# 2_ADSTM32_MCU.net
KiCad netlist of a schematic drawn in Altium Designer
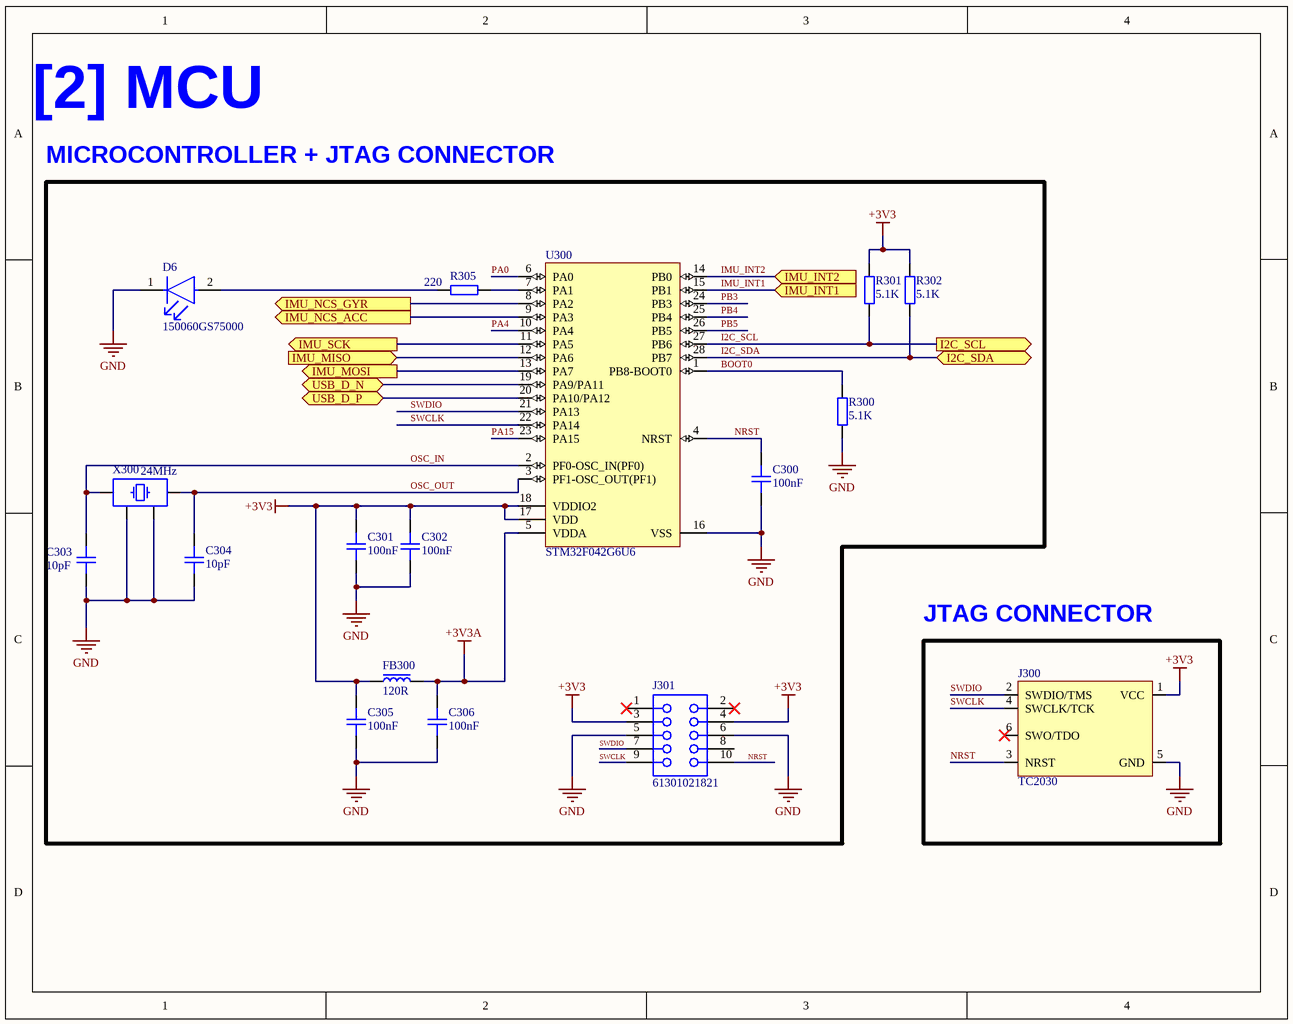
[diagram p0: 2_ADSTM32_MCU.SchDoc]

(export (version "E")
  (design (tool "Eeschema 10.0.6"))
  (components
    (comp (ref "C300")
      (value "100nF")
      (footprint "CAP_0603")
      (description "Capacitor SMD 0603 16V")
      (libsource (lib "Schematic-Lib-PhilsLab") (part "CAP_0603_16V"))
    )
    (comp (ref "C301")
      (value "100nF")
      (footprint "CAP_0603")
      (description "Capacitor SMD 0603 16V")
      (libsource (lib "Schematic-Lib-PhilsLab") (part "CAP_0603_16V"))
    )
    (comp (ref "C302")
      (value "100nF")
      (footprint "CAP_0603")
      (description "Capacitor SMD 0603 16V")
      (libsource (lib "Schematic-Lib-PhilsLab") (part "CAP_0603_16V"))
    )
    (comp (ref "C303")
      (value "10pF")
      (footprint "CAP_0603")
      (description "Capacitor SMD 0603 16V")
      (libsource (lib "Schematic-Lib-PhilsLab") (part "CAP_0603_16V"))
    )
    (comp (ref "C304")
      (value "10pF")
      (footprint "CAP_0603")
      (description "Capacitor SMD 0603 16V")
      (libsource (lib "Schematic-Lib-PhilsLab") (part "CAP_0603_16V"))
    )
    (comp (ref "C305")
      (value "100nF")
      (footprint "CAP_0603")
      (description "Capacitor SMD 0603 16V")
      (libsource (lib "Schematic-Lib-PhilsLab") (part "CAP_0603_16V"))
    )
    (comp (ref "C306")
      (value "100nF")
      (footprint "CAP_0603")
      (description "Capacitor SMD 0603 16V")
      (libsource (lib "Schematic-Lib-PhilsLab") (part "CAP_0603_16V"))
    )
    (comp (ref "D6")
      (value "150060GS75000")
      (footprint "FP-150060GS75000-MFG")
      (description "LED GREEN CLEAR 0603 SMD")
      (libsource (lib "Altium Content Vault") (part "8706943c75ba83719d021d2fdc84c58"))
    )
    (comp (ref "FB300")
      (value "120R")
      (footprint "FB_0603")
      (description "Ferrite Bead SMD 0603")
      (libsource (lib "Schematic-Lib-PhilsLab") (part "FB_0603"))
    )
    (comp (ref "J300")
      (value "TC2030")
      (footprint "TC2030-FP")
      (description "Tag-Connect No-Solder SWD Debug Connector DO NOT PLACE")
      (fields (field (name "MANUFACTURER") "Tag-Connect"))
      (libsource (lib "Schematic-Lib-PhilsLab") (part "TC2030"))
    )
    (comp (ref "J301")
      (value "61301021821")
      (footprint "61301021821")
      (libsource (lib "Altium Content Vault") (part "Header_Female_2R_10P"))
    )
    (comp (ref "R300")
      (value "5.1K")
      (footprint "RES_0603")
      (description "Resistor SMD 0603")
      (libsource (lib "Schematic-Lib-PhilsLab") (part "RES_0603"))
    )
    (comp (ref "R301")
      (value "5.1K")
      (footprint "RES_0603")
      (description "Resistor SMD 0603")
      (libsource (lib "Schematic-Lib-PhilsLab") (part "RES_0603"))
    )
    (comp (ref "R302")
      (value "5.1K")
      (footprint "RES_0603")
      (description "Resistor SMD 0603")
      (libsource (lib "Schematic-Lib-PhilsLab") (part "RES_0603"))
    )
    (comp (ref "R305")
      (value "220")
      (footprint "RES_0603")
      (description "Resistor SMD 0603")
      (libsource (lib "Schematic-Lib-PhilsLab") (part "RES_0603"))
    )
    (comp (ref "U300")
      (value "STM32F042G6U6")
      (footprint "STM-UFQFPN28_V")
      (fields (field (name "MANUFACTURER") "STMicroelectronics"))
      (libsource (lib "Altium Content Vault") (part "MC-ARM-STM32F042-UFQFPN28"))
    )
    (comp (ref "X300")
      (value "24MHz")
      (footprint "XTAL_3225")
      (description "Crystal SMD 24MHz 10PPM 7pF 3225")
      (fields
        (field (name "MANUFACTURER") "Epson")
        (field (name "MANUFACTURER PART NUMBER") "TSX-3225 24.0000MF15X-AC")
      )
      (libsource (lib "Schematic-Lib-PhilsLab") (part "TSX-3225_24.0000MF15X-AC"))
    )
  )
  (nets
    (net (code "1") (name "+3V3") (class "Default")
      (node (ref "C301") (pin "2") (pinfunction "2_2") (pintype "passive"))
      (node (ref "C302") (pin "2") (pinfunction "2_2") (pintype "passive"))
      (node (ref "C305") (pin "2") (pinfunction "2_2") (pintype "passive"))
      (node (ref "FB300") (pin "1") (pinfunction "1_1") (pintype "passive"))
      (node (ref "J300") (pin "1") (pinfunction "VCC_1") (pintype "passive"))
      (node (ref "J301") (pin "3") (pinfunction "3_3") (pintype "passive"))
      (node (ref "J301") (pin "4") (pinfunction "4_4") (pintype "passive"))
      (node (ref "R301") (pin "1") (pinfunction "1_1") (pintype "passive"))
      (node (ref "R302") (pin "1") (pinfunction "1_1") (pintype "passive"))
      (node (ref "U300") (pin "17") (pinfunction "VDD_17") (pintype "power_in"))
      (node (ref "U300") (pin "18") (pinfunction "VDDIO2_18") (pintype "power_in"))
    )
    (net (code "2") (name "+3V3A") (class "Default")
      (node (ref "C306") (pin "2") (pinfunction "2_2") (pintype "passive"))
      (node (ref "FB300") (pin "2") (pinfunction "2_2") (pintype "passive"))
      (node (ref "U300") (pin "5") (pinfunction "VDDA_5") (pintype "power_in"))
    )
    (net (code "3") (name "/BOOT0") (class "Default")
      (node (ref "R300") (pin "1") (pinfunction "1_1") (pintype "passive"))
      (node (ref "U300") (pin "1") (pinfunction "PB8-BOOT0_1") (pintype "bidirectional"))
    )
    (net (code "4") (name "/I2C_SCL") (class "Default")
      (node (ref "R301") (pin "2") (pinfunction "2_2") (pintype "passive"))
      (node (ref "U300") (pin "27") (pinfunction "PB6_27") (pintype "bidirectional"))
    )
    (net (code "5") (name "/I2C_SDA") (class "Default")
      (node (ref "R302") (pin "2") (pinfunction "2_2") (pintype "passive"))
      (node (ref "U300") (pin "28") (pinfunction "PB7_28") (pintype "bidirectional"))
    )
    (net (code "6") (name "/IMU_INT1") (class "Default")
      (node (ref "U300") (pin "15") (pinfunction "PB1_15") (pintype "bidirectional"))
    )
    (net (code "7") (name "/IMU_INT2") (class "Default")
      (node (ref "U300") (pin "14") (pinfunction "PB0_14") (pintype "bidirectional"))
    )
    (net (code "8") (name "/IMU_MISO") (class "Default")
      (node (ref "U300") (pin "12") (pinfunction "PA6_12") (pintype "bidirectional"))
    )
    (net (code "9") (name "/IMU_MOSI") (class "Default")
      (node (ref "U300") (pin "13") (pinfunction "PA7_13") (pintype "bidirectional"))
    )
    (net (code "10") (name "/IMU_NCS_ACC") (class "Default")
      (node (ref "U300") (pin "9") (pinfunction "PA3_9") (pintype "bidirectional"))
    )
    (net (code "11") (name "/IMU_NCS_GYR") (class "Default")
      (node (ref "U300") (pin "8") (pinfunction "PA2_8") (pintype "bidirectional"))
    )
    (net (code "12") (name "/IMU_SCK") (class "Default")
      (node (ref "U300") (pin "11") (pinfunction "PA5_11") (pintype "bidirectional"))
    )
    (net (code "13") (name "/NRST") (class "Default")
      (node (ref "C300") (pin "2") (pinfunction "2_2") (pintype "passive"))
      (node (ref "J300") (pin "3") (pinfunction "NRST_3") (pintype "passive"))
      (node (ref "J301") (pin "10") (pinfunction "10_10") (pintype "passive"))
      (node (ref "U300") (pin "4") (pinfunction "NRST_4") (pintype "bidirectional"))
    )
    (net (code "14") (name "/OSC_IN") (class "Default")
      (node (ref "C303") (pin "2") (pinfunction "2_2") (pintype "passive"))
      (node (ref "U300") (pin "2") (pinfunction "PF0-OSC_IN(PF0)_2") (pintype "bidirectional"))
      (node (ref "X300") (pin "1") (pinfunction "1_1") (pintype "passive"))
    )
    (net (code "15") (name "/OSC_OUT") (class "Default")
      (node (ref "C304") (pin "2") (pinfunction "2_2") (pintype "passive"))
      (node (ref "U300") (pin "3") (pinfunction "PF1-OSC_OUT(PF1)_3") (pintype "bidirectional"))
      (node (ref "X300") (pin "3") (pinfunction "3_3") (pintype "passive"))
    )
    (net (code "16") (name "/PA0") (class "Default")
      (node (ref "U300") (pin "6") (pinfunction "PA0_6") (pintype "bidirectional"))
    )
    (net (code "17") (name "/PA4") (class "Default")
      (node (ref "U300") (pin "10") (pinfunction "PA4_10") (pintype "bidirectional"))
    )
    (net (code "18") (name "/PA15") (class "Default")
      (node (ref "U300") (pin "23") (pinfunction "PA15_23") (pintype "bidirectional"))
    )
    (net (code "19") (name "/PB3") (class "Default")
      (node (ref "U300") (pin "24") (pinfunction "PB3_24") (pintype "bidirectional"))
    )
    (net (code "20") (name "/PB4") (class "Default")
      (node (ref "U300") (pin "25") (pinfunction "PB4_25") (pintype "bidirectional"))
    )
    (net (code "21") (name "/PB5") (class "Default")
      (node (ref "U300") (pin "26") (pinfunction "PB5_26") (pintype "bidirectional"))
    )
    (net (code "22") (name "/SWCLK") (class "Default")
      (node (ref "J300") (pin "4") (pinfunction "SWCLK/TCK_4") (pintype "passive"))
      (node (ref "J301") (pin "9") (pinfunction "9_9") (pintype "passive"))
      (node (ref "U300") (pin "22") (pinfunction "PA14_22") (pintype "bidirectional"))
    )
    (net (code "23") (name "/SWDIO") (class "Default")
      (node (ref "J300") (pin "2") (pinfunction "SWDIO/TMS_2") (pintype "passive"))
      (node (ref "J301") (pin "7") (pinfunction "7_7") (pintype "passive"))
      (node (ref "U300") (pin "21") (pinfunction "PA13_21") (pintype "bidirectional"))
    )
    (net (code "24") (name "/USB_D_N") (class "Default")
      (node (ref "U300") (pin "19") (pinfunction "PA9/PA11_19") (pintype "bidirectional"))
    )
    (net (code "25") (name "/USB_D_P") (class "Default")
      (node (ref "U300") (pin "20") (pinfunction "PA10/PA12_20") (pintype "bidirectional"))
    )
    (net (code "26") (name "GND") (class "Default")
      (node (ref "C300") (pin "1") (pinfunction "1_1") (pintype "passive"))
      (node (ref "C301") (pin "1") (pinfunction "1_1") (pintype "passive"))
      (node (ref "C302") (pin "1") (pinfunction "1_1") (pintype "passive"))
      (node (ref "C303") (pin "1") (pinfunction "1_1") (pintype "passive"))
      (node (ref "C304") (pin "1") (pinfunction "1_1") (pintype "passive"))
      (node (ref "C305") (pin "1") (pinfunction "1_1") (pintype "passive"))
      (node (ref "C306") (pin "1") (pinfunction "1_1") (pintype "passive"))
      (node (ref "D6") (pin "1") (pinfunction "C_1") (pintype "passive"))
      (node (ref "J300") (pin "5") (pinfunction "GND_5") (pintype "passive"))
      (node (ref "J301") (pin "5") (pinfunction "5_5") (pintype "passive"))
      (node (ref "J301") (pin "6") (pinfunction "6_6") (pintype "passive"))
      (node (ref "R300") (pin "2") (pinfunction "2_2") (pintype "passive"))
      (node (ref "U300") (pin "16") (pinfunction "VSS_16") (pintype "power_in"))
      (node (ref "X300") (pin "2") (pinfunction "2_2") (pintype "passive"))
      (node (ref "X300") (pin "4") (pinfunction "4_4") (pintype "passive"))
    )
    (net (code "27") (name "Net-(D6-A)") (class "Default")
      (node (ref "D6") (pin "2") (pinfunction "A_2") (pintype "passive"))
      (node (ref "R305") (pin "2") (pinfunction "2_2") (pintype "passive"))
    )
    (net (code "28") (name "Net-(U300-PA1)") (class "Default")
      (node (ref "R305") (pin "1") (pinfunction "1_1") (pintype "passive"))
      (node (ref "U300") (pin "7") (pinfunction "PA1_7") (pintype "bidirectional"))
    )
    (net (code "29") (name "unconnected-(J300-SWO{slash}TDO-Pad6)") (class "Default")
      (node (ref "J300") (pin "6") (pinfunction "SWO/TDO_6") (pintype "passive+no_connect"))
    )
    (net (code "30") (name "unconnected-(J301-Pad1)") (class "Default")
      (node (ref "J301") (pin "1") (pinfunction "1_1") (pintype "passive+no_connect"))
    )
    (net (code "31") (name "unconnected-(J301-Pad2)") (class "Default")
      (node (ref "J301") (pin "2") (pinfunction "2_2") (pintype "passive+no_connect"))
    )
    (net (code "32") (name "unconnected-(J301-Pad8)") (class "Default")
      (node (ref "J301") (pin "8") (pinfunction "8_8") (pintype "passive"))
    )
  )
)
